# BTS_and_Arduino_UNO_Shield.net
KiCad netlist of a schematic drawn in EAGLE
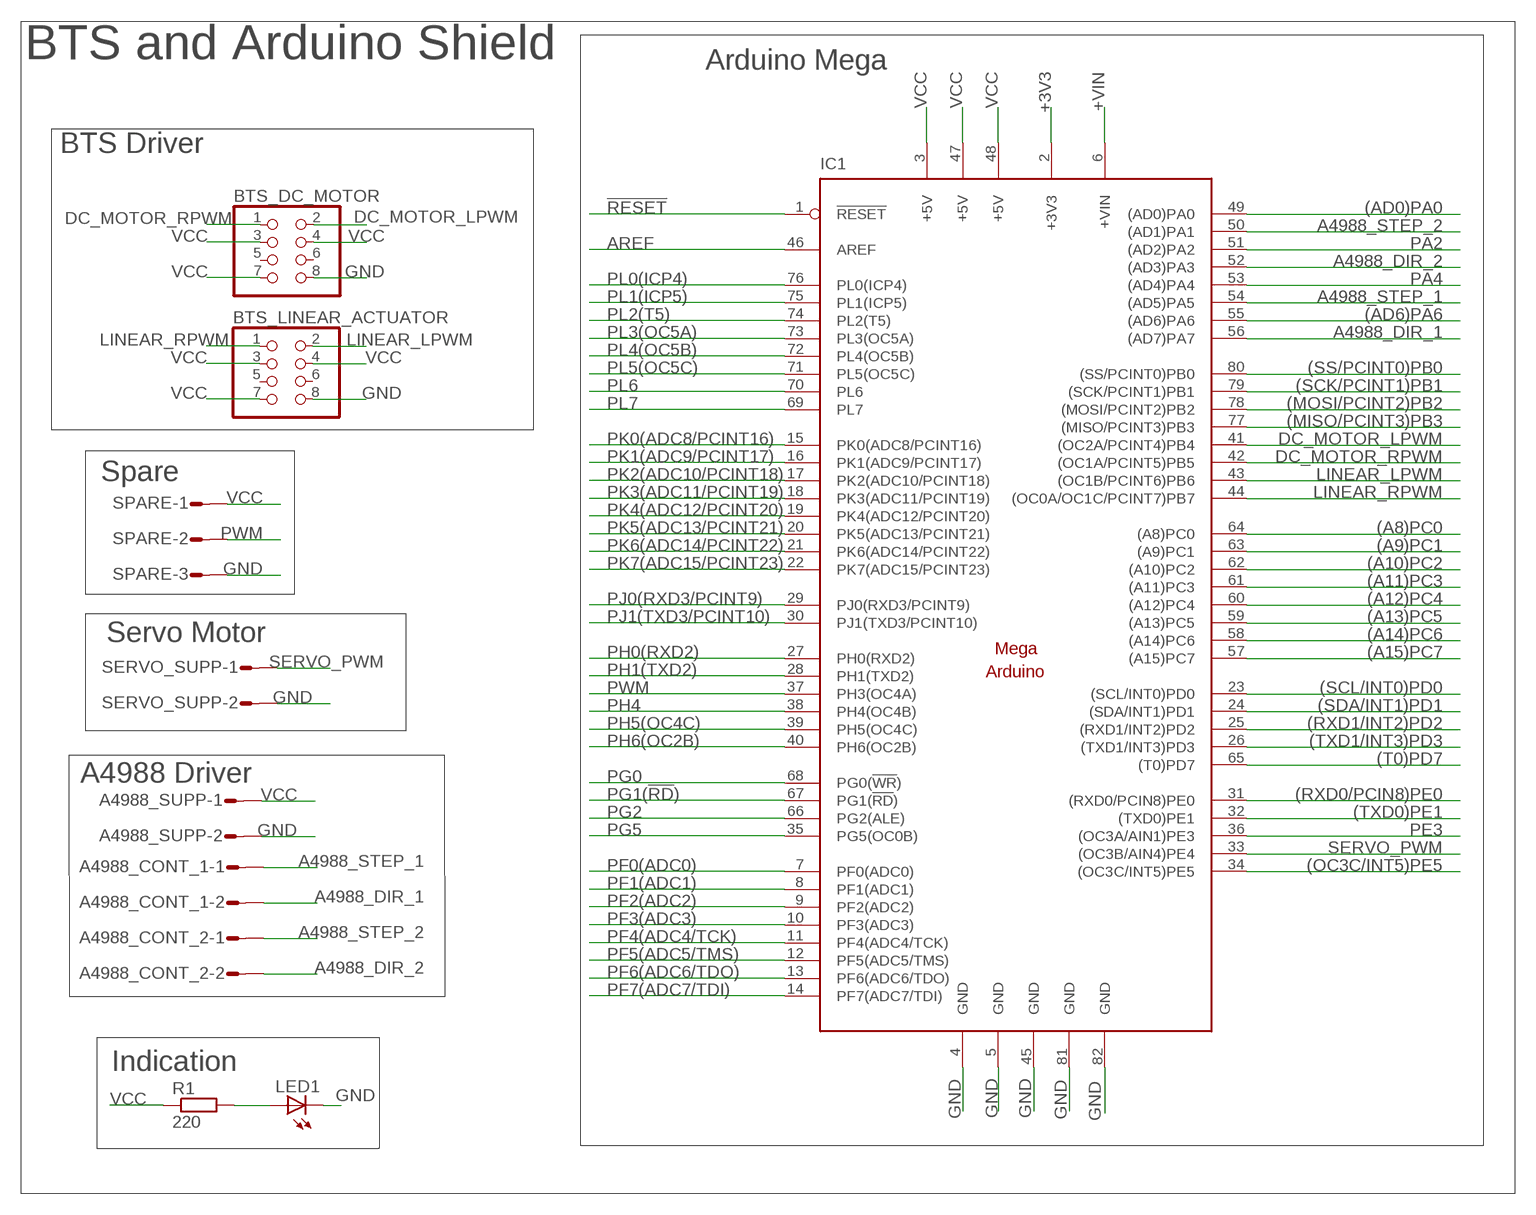
[diagram p0: schematic, sheet 1]

(export (version "E")
  (design (tool "Eeschema 10.0.6"))
  (components
    (comp (ref "A4988_CONT_1")
      (value "CON-AMP-MT_S02P")
      (footprint "eagle-import:CON-AMP-MT_S02P")
      (libsource (lib "eagle-import") (part "CON-AMP-MT_S02P"))
    )
    (comp (ref "A4988_CONT_2")
      (value "CON-AMP-MT_S02P")
      (footprint "eagle-import:CON-AMP-MT_S02P")
      (libsource (lib "eagle-import") (part "CON-AMP-MT_S02P"))
    )
    (comp (ref "A4988_SUPP")
      (value "CON-AMP-MT_S02P")
      (footprint "eagle-import:CON-AMP-MT_S02P")
      (libsource (lib "eagle-import") (part "CON-AMP-MT_S02P"))
    )
    (comp (ref "BTS_DC_MOTOR")
      (value "PINHD-2X4")
      (footprint "eagle-import:2X04")
      (libsource (lib "eagle-import") (part "PINHD-2X4"))
    )
    (comp (ref "BTS_LINEAR_ACTUATOR")
      (value "PINHD-2X4")
      (footprint "eagle-import:2X04")
      (libsource (lib "eagle-import") (part "PINHD-2X4"))
    )
    (comp (ref "IC1")
      (value "MEGAARDUINO_1")
      (footprint "eagle-import:MEGA_ARDUINO")
      (libsource (lib "eagle-import") (part "MEGAARDUINO_1"))
    )
    (comp (ref "LED1")
      (value "LED_LED3MM")
      (footprint "eagle-import:LED_LED3MM")
      (libsource (lib "eagle-import") (part "LED_LED3MM"))
    )
    (comp (ref "R1")
      (value "220")
      (footprint "eagle-import:RCL_0204_7")
      (libsource (lib "eagle-import") (part "RCL_R-EU_0204/7"))
    )
    (comp (ref "SERVO_SUPP")
      (value "CON-AMP-MT_S02P")
      (footprint "eagle-import:CON-AMP-MT_S02P")
      (libsource (lib "eagle-import") (part "CON-AMP-MT_S02P"))
    )
    (comp (ref "SPARE")
      (value "CON-AMP-MT_S03P")
      (footprint "eagle-import:CON-AMP-MT_S03P")
      (libsource (lib "eagle-import") (part "CON-AMP-MT_S03P"))
    )
  )
  (nets
    (net (code "1") (name "/(A8)PC0") (class "Default")
      (node (ref "IC1") (pin "64") (pinfunction "(A8)PC0_64") (pintype "bidirectional"))
    )
    (net (code "2") (name "/(A9)PC1") (class "Default")
      (node (ref "IC1") (pin "63") (pinfunction "(A9)PC1_63") (pintype "bidirectional"))
    )
    (net (code "3") (name "/(A10)PC2") (class "Default")
      (node (ref "IC1") (pin "62") (pinfunction "(A10)PC2_62") (pintype "bidirectional"))
    )
    (net (code "4") (name "/(A11)PC3") (class "Default")
      (node (ref "IC1") (pin "61") (pinfunction "(A11)PC3_61") (pintype "bidirectional"))
    )
    (net (code "5") (name "/(A12)PC4") (class "Default")
      (node (ref "IC1") (pin "60") (pinfunction "(A12)PC4_60") (pintype "bidirectional"))
    )
    (net (code "6") (name "/(A13)PC5") (class "Default")
      (node (ref "IC1") (pin "59") (pinfunction "(A13)PC5_59") (pintype "bidirectional"))
    )
    (net (code "7") (name "/(A14)PC6") (class "Default")
      (node (ref "IC1") (pin "58") (pinfunction "(A14)PC6_58") (pintype "bidirectional"))
    )
    (net (code "8") (name "/(A15)PC7") (class "Default")
      (node (ref "IC1") (pin "57") (pinfunction "(A15)PC7_57") (pintype "bidirectional"))
    )
    (net (code "9") (name "/(AD0)PA0") (class "Default")
      (node (ref "IC1") (pin "49") (pinfunction "(AD0)PA0_49") (pintype "bidirectional"))
    )
    (net (code "10") (name "/(AD6)PA6") (class "Default")
      (node (ref "IC1") (pin "55") (pinfunction "(AD6)PA6_55") (pintype "bidirectional"))
    )
    (net (code "11") (name "/(MISO{slash}PCINT3)PB3") (class "Default")
      (node (ref "IC1") (pin "77") (pinfunction "(MISO/PCINT3)PB3_77") (pintype "bidirectional"))
    )
    (net (code "12") (name "/(MOSI{slash}PCINT2)PB2") (class "Default")
      (node (ref "IC1") (pin "78") (pinfunction "(MOSI/PCINT2)PB2_78") (pintype "bidirectional"))
    )
    (net (code "13") (name "/(OC3C{slash}INT5)PE5") (class "Default")
      (node (ref "IC1") (pin "34") (pinfunction "(OC3C/INT5)PE5_34") (pintype "bidirectional"))
    )
    (net (code "14") (name "/(RXD0{slash}PCIN8)PE0") (class "Default")
      (node (ref "IC1") (pin "31") (pinfunction "(RXD0/PCIN8)PE0_31") (pintype "bidirectional"))
    )
    (net (code "15") (name "/(RXD1{slash}INT2)PD2") (class "Default")
      (node (ref "IC1") (pin "25") (pinfunction "(RXD1/INT2)PD2_25") (pintype "bidirectional"))
    )
    (net (code "16") (name "/(SCK{slash}PCINT1)PB1") (class "Default")
      (node (ref "IC1") (pin "79") (pinfunction "(SCK/PCINT1)PB1_79") (pintype "bidirectional"))
    )
    (net (code "17") (name "/(SCL{slash}INT0)PD0") (class "Default")
      (node (ref "IC1") (pin "23") (pinfunction "(SCL/INT0)PD0_23") (pintype "bidirectional"))
    )
    (net (code "18") (name "/(SDA{slash}INT1)PD1") (class "Default")
      (node (ref "IC1") (pin "24") (pinfunction "(SDA/INT1)PD1_24") (pintype "bidirectional"))
    )
    (net (code "19") (name "/(SS{slash}PCINT0)PB0") (class "Default")
      (node (ref "IC1") (pin "80") (pinfunction "(SS/PCINT0)PB0_80") (pintype "bidirectional"))
    )
    (net (code "20") (name "/(T0)PD7") (class "Default")
      (node (ref "IC1") (pin "65") (pinfunction "(T0)PD7_65") (pintype "bidirectional"))
    )
    (net (code "21") (name "/(TXD0)PE1") (class "Default")
      (node (ref "IC1") (pin "32") (pinfunction "(TXD0)PE1_32") (pintype "bidirectional"))
    )
    (net (code "22") (name "/(TXD1{slash}INT3)PD3") (class "Default")
      (node (ref "IC1") (pin "26") (pinfunction "(TXD1/INT3)PD3_26") (pintype "bidirectional"))
    )
    (net (code "23") (name "/+3V3") (class "Default")
      (node (ref "IC1") (pin "2") (pinfunction "+3V3_2") (pintype "power_in"))
    )
    (net (code "24") (name "/+VIN") (class "Default")
      (node (ref "IC1") (pin "6") (pinfunction "+VIN_6") (pintype "power_in"))
    )
    (net (code "25") (name "/A4988_DIR_1") (class "Default")
      (node (ref "A4988_CONT_1") (pin "2") (pinfunction "S_2") (pintype "passive"))
      (node (ref "IC1") (pin "56") (pinfunction "(AD7)PA7_56") (pintype "bidirectional"))
    )
    (net (code "26") (name "/A4988_DIR_2") (class "Default")
      (node (ref "A4988_CONT_2") (pin "2") (pinfunction "S_2") (pintype "passive"))
      (node (ref "IC1") (pin "52") (pinfunction "(AD3)PA3_52") (pintype "bidirectional"))
    )
    (net (code "27") (name "/A4988_STEP_1") (class "Default")
      (node (ref "A4988_CONT_1") (pin "1") (pinfunction "S_1") (pintype "passive"))
      (node (ref "IC1") (pin "54") (pinfunction "(AD5)PA5_54") (pintype "bidirectional"))
    )
    (net (code "28") (name "/A4988_STEP_2") (class "Default")
      (node (ref "A4988_CONT_2") (pin "1") (pinfunction "S_1") (pintype "passive"))
      (node (ref "IC1") (pin "50") (pinfunction "(AD1)PA1_50") (pintype "bidirectional"))
    )
    (net (code "29") (name "/AREF") (class "Default")
      (node (ref "IC1") (pin "46") (pinfunction "AREF_46") (pintype "bidirectional"))
    )
    (net (code "30") (name "/DC_MOTOR_LPWM") (class "Default")
      (node (ref "BTS_DC_MOTOR") (pin "2") (pinfunction "2_2") (pintype "passive"))
      (node (ref "IC1") (pin "41") (pinfunction "(OC2A/PCINT4)PB4_41") (pintype "bidirectional"))
    )
    (net (code "31") (name "/DC_MOTOR_RPWM") (class "Default")
      (node (ref "BTS_DC_MOTOR") (pin "1") (pinfunction "1_1") (pintype "passive"))
      (node (ref "IC1") (pin "42") (pinfunction "(OC1A/PCINT5)PB5_42") (pintype "bidirectional"))
    )
    (net (code "32") (name "/GND") (class "Default")
      (node (ref "A4988_SUPP") (pin "2") (pinfunction "S_2") (pintype "passive"))
      (node (ref "BTS_DC_MOTOR") (pin "8") (pinfunction "8_8") (pintype "passive"))
      (node (ref "BTS_LINEAR_ACTUATOR") (pin "8") (pinfunction "8_8") (pintype "passive"))
      (node (ref "IC1") (pin "4") (pinfunction "GND_4") (pintype "power_in"))
      (node (ref "IC1") (pin "45") (pinfunction "GND_45") (pintype "power_in"))
      (node (ref "IC1") (pin "5") (pinfunction "GND_5") (pintype "power_in"))
      (node (ref "IC1") (pin "81") (pinfunction "GND_81") (pintype "power_in"))
      (node (ref "IC1") (pin "82") (pinfunction "GND_82") (pintype "power_in"))
      (node (ref "LED1") (pin "K") (pinfunction "C_K") (pintype "passive"))
      (node (ref "SERVO_SUPP") (pin "2") (pinfunction "S_2") (pintype "passive"))
      (node (ref "SPARE") (pin "3") (pinfunction "S_3") (pintype "passive"))
    )
    (net (code "33") (name "/LINEAR_LPWM") (class "Default")
      (node (ref "BTS_LINEAR_ACTUATOR") (pin "2") (pinfunction "2_2") (pintype "passive"))
      (node (ref "IC1") (pin "43") (pinfunction "(OC1B/PCINT6)PB6_43") (pintype "bidirectional"))
    )
    (net (code "34") (name "/LINEAR_RPWM") (class "Default")
      (node (ref "BTS_LINEAR_ACTUATOR") (pin "1") (pinfunction "1_1") (pintype "passive"))
      (node (ref "IC1") (pin "44") (pinfunction "(OC0A/OC1C/PCINT7)PB7_44") (pintype "bidirectional"))
    )
    (net (code "35") (name "/PA2") (class "Default")
      (node (ref "IC1") (pin "51") (pinfunction "(AD2)PA2_51") (pintype "bidirectional"))
    )
    (net (code "36") (name "/PA4") (class "Default")
      (node (ref "IC1") (pin "53") (pinfunction "(AD4)PA4_53") (pintype "bidirectional"))
    )
    (net (code "37") (name "/PE3") (class "Default")
      (node (ref "IC1") (pin "36") (pinfunction "(OC3A/AIN1)PE3_36") (pintype "bidirectional"))
    )
    (net (code "38") (name "/PF0(ADC0)") (class "Default")
      (node (ref "IC1") (pin "7") (pinfunction "PF0(ADC0)_7") (pintype "bidirectional"))
    )
    (net (code "39") (name "/PF1(ADC1)") (class "Default")
      (node (ref "IC1") (pin "8") (pinfunction "PF1(ADC1)_8") (pintype "bidirectional"))
    )
    (net (code "40") (name "/PF2(ADC2)") (class "Default")
      (node (ref "IC1") (pin "9") (pinfunction "PF2(ADC2)_9") (pintype "bidirectional"))
    )
    (net (code "41") (name "/PF3(ADC3)") (class "Default")
      (node (ref "IC1") (pin "10") (pinfunction "PF3(ADC3)_10") (pintype "bidirectional"))
    )
    (net (code "42") (name "/PF4(ADC4{slash}TCK)") (class "Default")
      (node (ref "IC1") (pin "11") (pinfunction "PF4(ADC4/TCK)_11") (pintype "bidirectional"))
    )
    (net (code "43") (name "/PF5(ADC5{slash}TMS)") (class "Default")
      (node (ref "IC1") (pin "12") (pinfunction "PF5(ADC5/TMS)_12") (pintype "bidirectional"))
    )
    (net (code "44") (name "/PF6(ADC6{slash}TDO)") (class "Default")
      (node (ref "IC1") (pin "13") (pinfunction "PF6(ADC6/TDO)_13") (pintype "bidirectional"))
    )
    (net (code "45") (name "/PF7(ADC7{slash}TDI)") (class "Default")
      (node (ref "IC1") (pin "14") (pinfunction "PF7(ADC7/TDI)_14") (pintype "bidirectional"))
    )
    (net (code "46") (name "/PG0") (class "Default")
      (node (ref "IC1") (pin "68") (pinfunction "PG0(~{WR})_68") (pintype "bidirectional"))
    )
    (net (code "47") (name "/PG1(~{RD})") (class "Default")
      (node (ref "IC1") (pin "67") (pinfunction "PG1(~{RD})_67") (pintype "bidirectional"))
    )
    (net (code "48") (name "/PG2") (class "Default")
      (node (ref "IC1") (pin "66") (pinfunction "PG2(ALE)_66") (pintype "bidirectional"))
    )
    (net (code "49") (name "/PG5") (class "Default")
      (node (ref "IC1") (pin "35") (pinfunction "PG5(OC0B)_35") (pintype "bidirectional"))
    )
    (net (code "50") (name "/PH0(RXD2)") (class "Default")
      (node (ref "IC1") (pin "27") (pinfunction "PH0(RXD2)_27") (pintype "bidirectional"))
    )
    (net (code "51") (name "/PH1(TXD2)") (class "Default")
      (node (ref "IC1") (pin "28") (pinfunction "PH1(TXD2)_28") (pintype "bidirectional"))
    )
    (net (code "52") (name "/PH4") (class "Default")
      (node (ref "IC1") (pin "38") (pinfunction "PH4(OC4B)_38") (pintype "bidirectional"))
    )
    (net (code "53") (name "/PH5(OC4C)") (class "Default")
      (node (ref "IC1") (pin "39") (pinfunction "PH5(OC4C)_39") (pintype "bidirectional"))
    )
    (net (code "54") (name "/PH6(OC2B)") (class "Default")
      (node (ref "IC1") (pin "40") (pinfunction "PH6(OC2B)_40") (pintype "bidirectional"))
    )
    (net (code "55") (name "/PJ0(RXD3{slash}PCINT9)") (class "Default")
      (node (ref "IC1") (pin "29") (pinfunction "PJ0(RXD3/PCINT9)_29") (pintype "bidirectional"))
    )
    (net (code "56") (name "/PJ1(TXD3{slash}PCINT10)") (class "Default")
      (node (ref "IC1") (pin "30") (pinfunction "PJ1(TXD3/PCINT10)_30") (pintype "bidirectional"))
    )
    (net (code "57") (name "/PK0(ADC8{slash}PCINT16)") (class "Default")
      (node (ref "IC1") (pin "15") (pinfunction "PK0(ADC8/PCINT16)_15") (pintype "bidirectional"))
    )
    (net (code "58") (name "/PK1(ADC9{slash}PCINT17)") (class "Default")
      (node (ref "IC1") (pin "16") (pinfunction "PK1(ADC9/PCINT17)_16") (pintype "bidirectional"))
    )
    (net (code "59") (name "/PK2(ADC10{slash}PCINT18)") (class "Default")
      (node (ref "IC1") (pin "17") (pinfunction "PK2(ADC10/PCINT18)_17") (pintype "bidirectional"))
    )
    (net (code "60") (name "/PK3(ADC11{slash}PCINT19)") (class "Default")
      (node (ref "IC1") (pin "18") (pinfunction "PK3(ADC11/PCINT19)_18") (pintype "bidirectional"))
    )
    (net (code "61") (name "/PK4(ADC12{slash}PCINT20)") (class "Default")
      (node (ref "IC1") (pin "19") (pinfunction "PK4(ADC12/PCINT20)_19") (pintype "bidirectional"))
    )
    (net (code "62") (name "/PK5(ADC13{slash}PCINT21)") (class "Default")
      (node (ref "IC1") (pin "20") (pinfunction "PK5(ADC13/PCINT21)_20") (pintype "bidirectional"))
    )
    (net (code "63") (name "/PK6(ADC14{slash}PCINT22)") (class "Default")
      (node (ref "IC1") (pin "21") (pinfunction "PK6(ADC14/PCINT22)_21") (pintype "bidirectional"))
    )
    (net (code "64") (name "/PK7(ADC15{slash}PCINT23)") (class "Default")
      (node (ref "IC1") (pin "22") (pinfunction "PK7(ADC15/PCINT23)_22") (pintype "bidirectional"))
    )
    (net (code "65") (name "/PL0(ICP4)") (class "Default")
      (node (ref "IC1") (pin "76") (pinfunction "PL0(ICP4)_76") (pintype "bidirectional"))
    )
    (net (code "66") (name "/PL1(ICP5)") (class "Default")
      (node (ref "IC1") (pin "75") (pinfunction "PL1(ICP5)_75") (pintype "bidirectional"))
    )
    (net (code "67") (name "/PL2(T5)") (class "Default")
      (node (ref "IC1") (pin "74") (pinfunction "PL2(T5)_74") (pintype "bidirectional"))
    )
    (net (code "68") (name "/PL3(OC5A)") (class "Default")
      (node (ref "IC1") (pin "73") (pinfunction "PL3(OC5A)_73") (pintype "bidirectional"))
    )
    (net (code "69") (name "/PL4(OC5B)") (class "Default")
      (node (ref "IC1") (pin "72") (pinfunction "PL4(OC5B)_72") (pintype "bidirectional"))
    )
    (net (code "70") (name "/PL5(OC5C)") (class "Default")
      (node (ref "IC1") (pin "71") (pinfunction "PL5(OC5C)_71") (pintype "bidirectional"))
    )
    (net (code "71") (name "/PL6") (class "Default")
      (node (ref "IC1") (pin "70") (pinfunction "PL6_70") (pintype "bidirectional"))
    )
    (net (code "72") (name "/PL7") (class "Default")
      (node (ref "IC1") (pin "69") (pinfunction "PL7_69") (pintype "bidirectional"))
    )
    (net (code "73") (name "/PWM") (class "Default")
      (node (ref "IC1") (pin "37") (pinfunction "PH3(OC4A)_37") (pintype "bidirectional"))
      (node (ref "SPARE") (pin "2") (pinfunction "S_2") (pintype "passive"))
    )
    (net (code "74") (name "/SERVO_PWM") (class "Default")
      (node (ref "IC1") (pin "33") (pinfunction "(OC3B/AIN4)PE4_33") (pintype "bidirectional"))
      (node (ref "SERVO_SUPP") (pin "1") (pinfunction "S_1") (pintype "passive"))
    )
    (net (code "75") (name "/VCC") (class "Default")
      (node (ref "A4988_SUPP") (pin "1") (pinfunction "S_1") (pintype "passive"))
      (node (ref "BTS_DC_MOTOR") (pin "3") (pinfunction "3_3") (pintype "passive"))
      (node (ref "BTS_DC_MOTOR") (pin "4") (pinfunction "4_4") (pintype "passive"))
      (node (ref "BTS_DC_MOTOR") (pin "7") (pinfunction "7_7") (pintype "passive"))
      (node (ref "BTS_LINEAR_ACTUATOR") (pin "3") (pinfunction "3_3") (pintype "passive"))
      (node (ref "BTS_LINEAR_ACTUATOR") (pin "4") (pinfunction "4_4") (pintype "passive"))
      (node (ref "BTS_LINEAR_ACTUATOR") (pin "7") (pinfunction "7_7") (pintype "passive"))
      (node (ref "IC1") (pin "3") (pinfunction "+5V_3") (pintype "power_in"))
      (node (ref "IC1") (pin "47") (pinfunction "+5V_47") (pintype "power_in"))
      (node (ref "IC1") (pin "48") (pinfunction "+5V_48") (pintype "power_in"))
      (node (ref "R1") (pin "1") (pinfunction "1_1") (pintype "passive"))
      (node (ref "SPARE") (pin "1") (pinfunction "S_1") (pintype "passive"))
    )
    (net (code "76") (name "/~{RESET}") (class "Default")
      (node (ref "IC1") (pin "1") (pinfunction "~{RESET}_1") (pintype "bidirectional"))
    )
    (net (code "77") (name "Net-(LED1-PadA)") (class "Default")
      (node (ref "LED1") (pin "A") (pinfunction "A_A") (pintype "passive"))
      (node (ref "R1") (pin "2") (pinfunction "2_2") (pintype "passive"))
    )
    (net (code "78") (name "unconnected-(BTS_DC_MOTOR-Pad5)") (class "Default")
      (node (ref "BTS_DC_MOTOR") (pin "5") (pinfunction "5_5") (pintype "passive"))
    )
    (net (code "79") (name "unconnected-(BTS_DC_MOTOR-Pad6)") (class "Default")
      (node (ref "BTS_DC_MOTOR") (pin "6") (pinfunction "6_6") (pintype "passive"))
    )
    (net (code "80") (name "unconnected-(BTS_LINEAR_ACTUATOR-Pad5)") (class "Default")
      (node (ref "BTS_LINEAR_ACTUATOR") (pin "5") (pinfunction "5_5") (pintype "passive"))
    )
    (net (code "81") (name "unconnected-(BTS_LINEAR_ACTUATOR-Pad6)") (class "Default")
      (node (ref "BTS_LINEAR_ACTUATOR") (pin "6") (pinfunction "6_6") (pintype "passive"))
    )
  )
)
